# mainSchem.net
KiCad netlist of a schematic drawn in Altium Designer
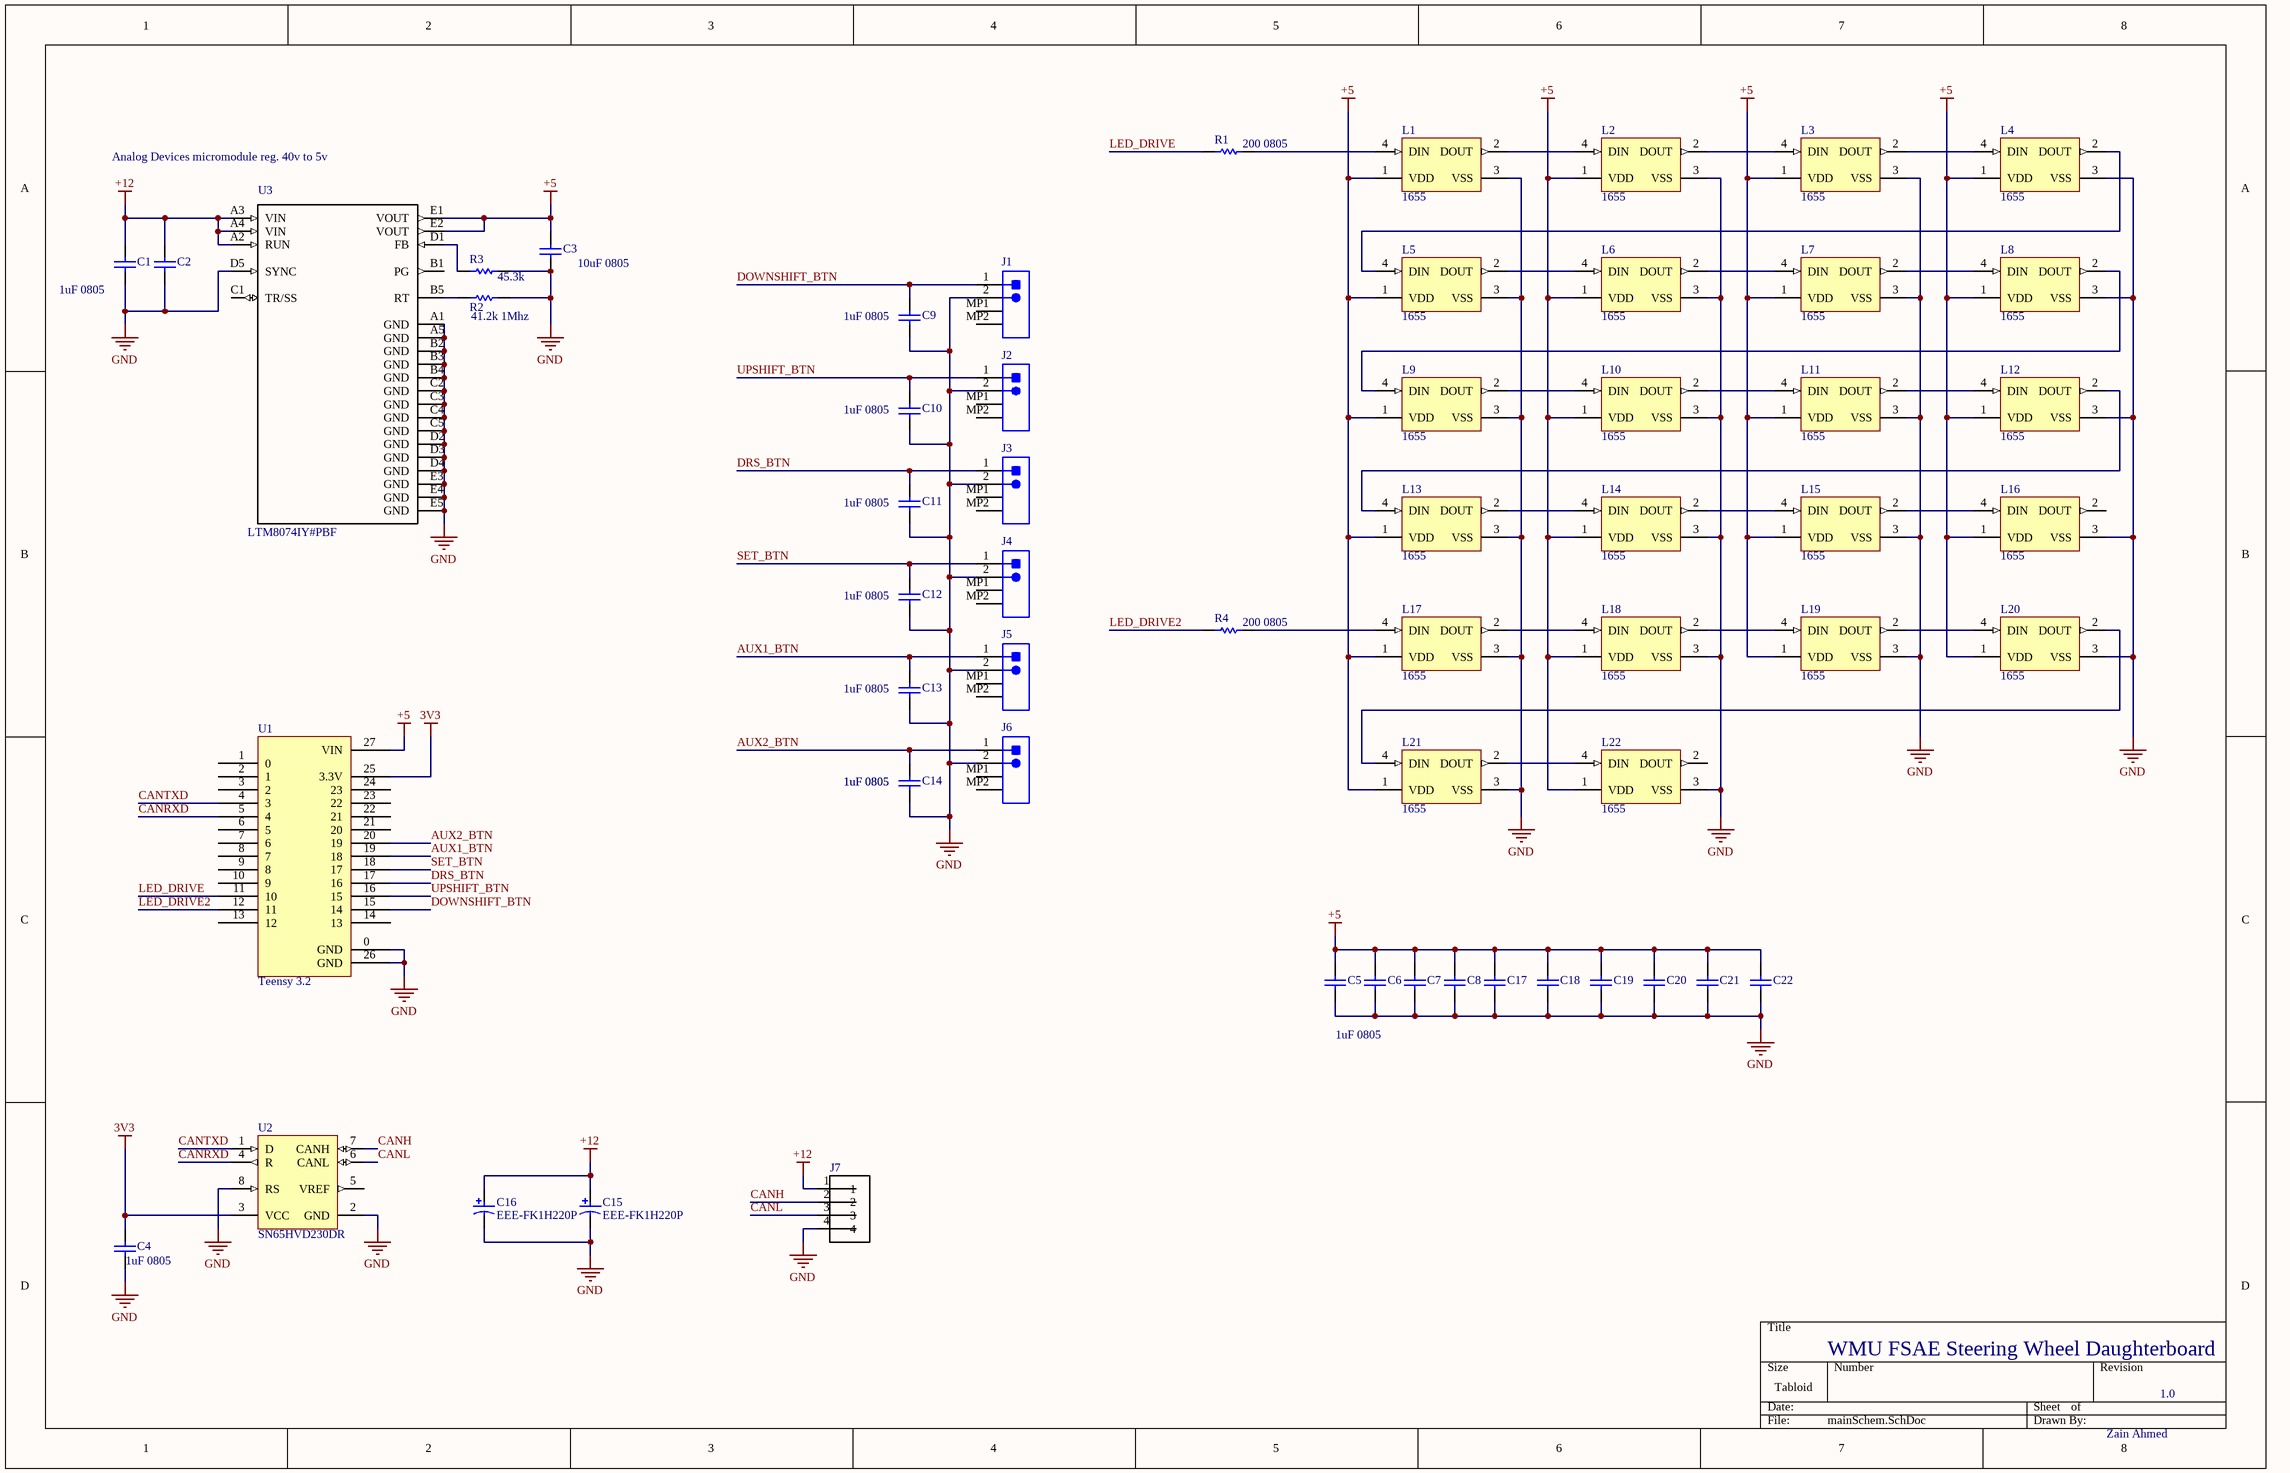
[diagram p0: mainSchem.SchDoc]

(export (version "E")
  (design (tool "Eeschema 10.0.6"))
  (components
    (comp (ref "C1")
      (value "GRM216R61E105KA12D")
      (footprint "CAPC2013X70X45NL10T25")
      (fields (field (name "MANUFACTURER") "Murata"))
      (libsource (lib "Altium Content Vault") (part "CAP"))
    )
    (comp (ref "C2")
      (value "GRM216R61E105KA12D")
      (footprint "CAPC2013X70X45NL10T25")
      (fields (field (name "MANUFACTURER") "Murata"))
      (libsource (lib "Altium Content Vault") (part "CAP"))
    )
    (comp (ref "C3")
      (value "GRM21BR61C106KE15L")
      (footprint "CAPC2013X135X50LL10T20")
      (fields (field (name "MANUFACTURER") "Murata"))
      (libsource (lib "Altium Content Vault") (part "CAP"))
    )
    (comp (ref "C4")
      (value "GRM216R61E105KA12D")
      (footprint "CAPC2013X70X45NL10T25")
      (fields (field (name "MANUFACTURER") "Murata"))
      (libsource (lib "Altium Content Vault") (part "CAP"))
    )
    (comp (ref "C5")
      (value "GRM216R61E105KA12D")
      (footprint "CAPC2013X70X45NL10T25")
      (fields (field (name "MANUFACTURER") "Murata"))
      (libsource (lib "Altium Content Vault") (part "CAP"))
    )
    (comp (ref "C6")
      (value "GRM216R61E105KA12D")
      (footprint "CAPC2013X70X45NL10T25")
      (fields (field (name "MANUFACTURER") "Murata"))
      (libsource (lib "Altium Content Vault") (part "CAP"))
    )
    (comp (ref "C7")
      (value "GRM216R61E105KA12D")
      (footprint "CAPC2013X70X45NL10T25")
      (fields (field (name "MANUFACTURER") "Murata"))
      (libsource (lib "Altium Content Vault") (part "CAP"))
    )
    (comp (ref "C8")
      (value "GRM216R61E105KA12D")
      (footprint "CAPC2013X70X45NL10T25")
      (fields (field (name "MANUFACTURER") "Murata"))
      (libsource (lib "Altium Content Vault") (part "CAP"))
    )
    (comp (ref "C9")
      (value "GRM216R61E105KA12D")
      (footprint "CAPC2013X70X45NL10T25")
      (fields (field (name "MANUFACTURER") "Murata"))
      (libsource (lib "Altium Content Vault") (part "CAP"))
    )
    (comp (ref "C10")
      (value "GRM216R61E105KA12D")
      (footprint "CAPC2013X70X45NL10T25")
      (fields (field (name "MANUFACTURER") "Murata"))
      (libsource (lib "Altium Content Vault") (part "CAP"))
    )
    (comp (ref "C11")
      (value "GRM216R61E105KA12D")
      (footprint "CAPC2013X70X45NL10T25")
      (fields (field (name "MANUFACTURER") "Murata"))
      (libsource (lib "Altium Content Vault") (part "CAP"))
    )
    (comp (ref "C12")
      (value "GRM216R61E105KA12D")
      (footprint "CAPC2013X70X45NL10T25")
      (fields (field (name "MANUFACTURER") "Murata"))
      (libsource (lib "Altium Content Vault") (part "CAP"))
    )
    (comp (ref "C13")
      (value "GRM216R61E105KA12D")
      (footprint "CAPC2013X70X45NL10T25")
      (fields (field (name "MANUFACTURER") "Murata"))
      (libsource (lib "Altium Content Vault") (part "CAP"))
    )
    (comp (ref "C14")
      (value "GRM216R61E105KA12D")
      (footprint "CAPC2013X70X45NL10T25")
      (fields (field (name "MANUFACTURER") "Murata"))
      (libsource (lib "Altium Content Vault") (part "CAP"))
    )
    (comp (ref "C15")
      (value "EEE-FK1H220P")
      (footprint "PNSC-EEE-FK1H220P_L")
      (description "Cap Aluminum Lytic, 22 uF, +/- 20%, 6.3 to 100 V, -55 to 105 degC, 2-Pin SMD, RoHS, Tape and Reel")
      (fields (field (name "MANUFACTURER") "Panasonic"))
      (libsource (lib "Altium Content Vault") (part "CAP-P-2"))
    )
    (comp (ref "C16")
      (value "EEE-FK1H220P")
      (footprint "PNSC-EEE-FK1H220P_L")
      (description "Cap Aluminum Lytic, 22 uF, +/- 20%, 6.3 to 100 V, -55 to 105 degC, 2-Pin SMD, RoHS, Tape and Reel")
      (fields (field (name "MANUFACTURER") "Panasonic"))
      (libsource (lib "Altium Content Vault") (part "CAP-P-2"))
    )
    (comp (ref "C17")
      (value "GRM216R61E105KA12D")
      (footprint "CAPC2013X70X45NL10T25")
      (fields (field (name "MANUFACTURER") "Murata"))
      (libsource (lib "Altium Content Vault") (part "CAP"))
    )
    (comp (ref "C18")
      (value "GRM216R61E105KA12D")
      (footprint "CAPC2013X70X45NL10T25")
      (fields (field (name "MANUFACTURER") "Murata"))
      (libsource (lib "Altium Content Vault") (part "CAP"))
    )
    (comp (ref "C19")
      (value "GRM216R61E105KA12D")
      (footprint "CAPC2013X70X45NL10T25")
      (fields (field (name "MANUFACTURER") "Murata"))
      (libsource (lib "Altium Content Vault") (part "CAP"))
    )
    (comp (ref "C20")
      (value "GRM216R61E105KA12D")
      (footprint "CAPC2013X70X45NL10T25")
      (fields (field (name "MANUFACTURER") "Murata"))
      (libsource (lib "Altium Content Vault") (part "CAP"))
    )
    (comp (ref "C21")
      (value "GRM216R61E105KA12D")
      (footprint "CAPC2013X70X45NL10T25")
      (fields (field (name "MANUFACTURER") "Murata"))
      (libsource (lib "Altium Content Vault") (part "CAP"))
    )
    (comp (ref "C22")
      (value "GRM216R61E105KA12D")
      (footprint "CAPC2013X70X45NL10T25")
      (fields (field (name "MANUFACTURER") "Murata"))
      (libsource (lib "Altium Content Vault") (part "CAP"))
    )
    (comp (ref "J1")
      (value "B2B-PH-SM4-TB(LF)(SN)")
      (footprint "JST-B2B-PH-SM4-TB-2_V")
      (description "Male Header, Pitch 2 mm, 1 x 2 Position, Height 6.6 mm, RoHS, Tape and Reel")
      (fields (field (name "MANUFACTURER") "JST"))
      (libsource (lib "Altium Content Vault") (part "CN-1P-2M-R2"))
    )
    (comp (ref "J2")
      (value "B2B-PH-SM4-TB(LF)(SN)")
      (footprint "JST-B2B-PH-SM4-TB-2_V")
      (description "Male Header, Pitch 2 mm, 1 x 2 Position, Height 6.6 mm, RoHS, Tape and Reel")
      (fields (field (name "MANUFACTURER") "JST"))
      (libsource (lib "Altium Content Vault") (part "CN-1P-2M-R2"))
    )
    (comp (ref "J3")
      (value "B2B-PH-SM4-TB(LF)(SN)")
      (footprint "JST-B2B-PH-SM4-TB-2_V")
      (description "Male Header, Pitch 2 mm, 1 x 2 Position, Height 6.6 mm, RoHS, Tape and Reel")
      (fields (field (name "MANUFACTURER") "JST"))
      (libsource (lib "Altium Content Vault") (part "CN-1P-2M-R2"))
    )
    (comp (ref "J4")
      (value "B2B-PH-SM4-TB(LF)(SN)")
      (footprint "JST-B2B-PH-SM4-TB-2_V")
      (description "Male Header, Pitch 2 mm, 1 x 2 Position, Height 6.6 mm, RoHS, Tape and Reel")
      (fields (field (name "MANUFACTURER") "JST"))
      (libsource (lib "Altium Content Vault") (part "CN-1P-2M-R2"))
    )
    (comp (ref "J5")
      (value "B2B-PH-SM4-TB(LF)(SN)")
      (footprint "JST-B2B-PH-SM4-TB-2_V")
      (description "Male Header, Pitch 2 mm, 1 x 2 Position, Height 6.6 mm, RoHS, Tape and Reel")
      (fields (field (name "MANUFACTURER") "JST"))
      (libsource (lib "Altium Content Vault") (part "CN-1P-2M-R2"))
    )
    (comp (ref "J6")
      (value "B2B-PH-SM4-TB(LF)(SN)")
      (footprint "JST-B2B-PH-SM4-TB-2_V")
      (description "Male Header, Pitch 2 mm, 1 x 2 Position, Height 6.6 mm, RoHS, Tape and Reel")
      (fields (field (name "MANUFACTURER") "JST"))
      (libsource (lib "Altium Content Vault") (part "CN-1P-2M-R2"))
    )
    (comp (ref "J7")
      (value "B4B-PH-SM4-TB")
      (footprint "*JST_B4B-PH-SM4-TB")
      (description "Connector Header Surface Mount 4 position 0.079 _2.00mm_")
      (fields (field (name "MF") "JST Sales"))
      (libsource (lib "B4B-PH-SM4-TB") (part "B4B-PH-SM4-TB"))
    )
    (comp (ref "L1")
      (value "1655")
      (footprint "ADA-RGB-1655_V")
      (fields (field (name "MANUFACTURER") "Adafruit-Industries-LLC"))
      (libsource (lib "Altium Content Vault") (part "ADA-RGB-1655-4"))
    )
    (comp (ref "L2")
      (value "1655")
      (footprint "ADA-RGB-1655_V")
      (fields (field (name "MANUFACTURER") "Adafruit-Industries-LLC"))
      (libsource (lib "Altium Content Vault") (part "ADA-RGB-1655-4"))
    )
    (comp (ref "L3")
      (value "1655")
      (footprint "ADA-RGB-1655_V")
      (fields (field (name "MANUFACTURER") "Adafruit-Industries-LLC"))
      (libsource (lib "Altium Content Vault") (part "ADA-RGB-1655-4"))
    )
    (comp (ref "L4")
      (value "1655")
      (footprint "ADA-RGB-1655_V")
      (fields (field (name "MANUFACTURER") "Adafruit-Industries-LLC"))
      (libsource (lib "Altium Content Vault") (part "ADA-RGB-1655-4"))
    )
    (comp (ref "L5")
      (value "1655")
      (footprint "ADA-RGB-1655_V")
      (fields (field (name "MANUFACTURER") "Adafruit-Industries-LLC"))
      (libsource (lib "Altium Content Vault") (part "ADA-RGB-1655-4"))
    )
    (comp (ref "L6")
      (value "1655")
      (footprint "ADA-RGB-1655_V")
      (fields (field (name "MANUFACTURER") "Adafruit-Industries-LLC"))
      (libsource (lib "Altium Content Vault") (part "ADA-RGB-1655-4"))
    )
    (comp (ref "L7")
      (value "1655")
      (footprint "ADA-RGB-1655_V")
      (fields (field (name "MANUFACTURER") "Adafruit-Industries-LLC"))
      (libsource (lib "Altium Content Vault") (part "ADA-RGB-1655-4"))
    )
    (comp (ref "L8")
      (value "1655")
      (footprint "ADA-RGB-1655_V")
      (fields (field (name "MANUFACTURER") "Adafruit-Industries-LLC"))
      (libsource (lib "Altium Content Vault") (part "ADA-RGB-1655-4"))
    )
    (comp (ref "L9")
      (value "1655")
      (footprint "ADA-RGB-1655_V")
      (fields (field (name "MANUFACTURER") "Adafruit-Industries-LLC"))
      (libsource (lib "Altium Content Vault") (part "ADA-RGB-1655-4"))
    )
    (comp (ref "L10")
      (value "1655")
      (footprint "ADA-RGB-1655_V")
      (fields (field (name "MANUFACTURER") "Adafruit-Industries-LLC"))
      (libsource (lib "Altium Content Vault") (part "ADA-RGB-1655-4"))
    )
    (comp (ref "L11")
      (value "1655")
      (footprint "ADA-RGB-1655_V")
      (fields (field (name "MANUFACTURER") "Adafruit-Industries-LLC"))
      (libsource (lib "Altium Content Vault") (part "ADA-RGB-1655-4"))
    )
    (comp (ref "L12")
      (value "1655")
      (footprint "ADA-RGB-1655_V")
      (fields (field (name "MANUFACTURER") "Adafruit-Industries-LLC"))
      (libsource (lib "Altium Content Vault") (part "ADA-RGB-1655-4"))
    )
    (comp (ref "L13")
      (value "1655")
      (footprint "ADA-RGB-1655_V")
      (fields (field (name "MANUFACTURER") "Adafruit-Industries-LLC"))
      (libsource (lib "Altium Content Vault") (part "ADA-RGB-1655-4"))
    )
    (comp (ref "L14")
      (value "1655")
      (footprint "ADA-RGB-1655_V")
      (fields (field (name "MANUFACTURER") "Adafruit-Industries-LLC"))
      (libsource (lib "Altium Content Vault") (part "ADA-RGB-1655-4"))
    )
    (comp (ref "L15")
      (value "1655")
      (footprint "ADA-RGB-1655_V")
      (fields (field (name "MANUFACTURER") "Adafruit-Industries-LLC"))
      (libsource (lib "Altium Content Vault") (part "ADA-RGB-1655-4"))
    )
    (comp (ref "L16")
      (value "1655")
      (footprint "ADA-RGB-1655_V")
      (fields (field (name "MANUFACTURER") "Adafruit-Industries-LLC"))
      (libsource (lib "Altium Content Vault") (part "ADA-RGB-1655-4"))
    )
    (comp (ref "L17")
      (value "1655")
      (footprint "ADA-RGB-1655_V")
      (fields (field (name "MANUFACTURER") "Adafruit-Industries-LLC"))
      (libsource (lib "Altium Content Vault") (part "ADA-RGB-1655-4"))
    )
    (comp (ref "L18")
      (value "1655")
      (footprint "ADA-RGB-1655_V")
      (fields (field (name "MANUFACTURER") "Adafruit-Industries-LLC"))
      (libsource (lib "Altium Content Vault") (part "ADA-RGB-1655-4"))
    )
    (comp (ref "L19")
      (value "1655")
      (footprint "ADA-RGB-1655_V")
      (fields (field (name "MANUFACTURER") "Adafruit-Industries-LLC"))
      (libsource (lib "Altium Content Vault") (part "ADA-RGB-1655-4"))
    )
    (comp (ref "L20")
      (value "1655")
      (footprint "ADA-RGB-1655_V")
      (fields (field (name "MANUFACTURER") "Adafruit-Industries-LLC"))
      (libsource (lib "Altium Content Vault") (part "ADA-RGB-1655-4"))
    )
    (comp (ref "L21")
      (value "1655")
      (footprint "ADA-RGB-1655_V")
      (fields (field (name "MANUFACTURER") "Adafruit-Industries-LLC"))
      (libsource (lib "Altium Content Vault") (part "ADA-RGB-1655-4"))
    )
    (comp (ref "L22")
      (value "1655")
      (footprint "ADA-RGB-1655_V")
      (fields (field (name "MANUFACTURER") "Adafruit-Industries-LLC"))
      (libsource (lib "Altium Content Vault") (part "ADA-RGB-1655-4"))
    )
    (comp (ref "R1")
      (value "ERA6AEB201V")
      (footprint "RESC2013X60X40NL20T25")
      (fields (field (name "MANUFACTURER") "Panasonic"))
      (libsource (lib "Altium Content Vault") (part "RES"))
    )
    (comp (ref "R2")
      (value "ERJ-6ENF4122V")
      (footprint "RESC2013X70X40LL20T20")
      (fields (field (name "MANUFACTURER") "Panasonic"))
      (libsource (lib "Altium Content Vault") (part "RES"))
    )
    (comp (ref "R3")
      (value "ERJ-6ENF4532V")
      (footprint "RESC2013X70X40ML20T20")
      (fields (field (name "MANUFACTURER") "Panasonic"))
      (libsource (lib "Altium Content Vault") (part "RES"))
    )
    (comp (ref "R4")
      (value "ERA6AEB201V")
      (footprint "RESC2013X60X40NL20T25")
      (fields (field (name "MANUFACTURER") "Panasonic"))
      (libsource (lib "Altium Content Vault") (part "RES"))
    )
    (comp (ref "U1")
      (value "Teensy 3.2")
      (footprint "Teensy3_2")
      (libsource (lib "Teensy3_2") (part "Teensy 3.2"))
    )
    (comp (ref "U2")
      (value "SN65HVD230DR")
      (footprint "D0008A_L")
      (fields (field (name "MANUFACTURER") "Texas Instruments"))
      (libsource (lib "Altium Content Vault") (part "TI-SN65HVD230-SOIC_D-8"))
    )
    (comp (ref "U3")
      (value "LTM8074IY#PBF")
      (footprint "*BGA25C65P5X5_400X400X198N_LTM8074IY#PBF(Primary)")
      (description "40Vin, 0.7A Step Dwn uModule Reg")
      (fields (field (name "MF") "Analog Devices"))
      (libsource (lib "LTM8074IY_PBF") (part "LTM8074IY#PBF"))
    )
  )
  (nets
    (net (code "1") (name "+5") (class "Default")
      (node (ref "C17") (pin "1") (pinfunction "1_1") (pintype "passive"))
      (node (ref "C18") (pin "1") (pinfunction "1_1") (pintype "passive"))
      (node (ref "C19") (pin "1") (pinfunction "1_1") (pintype "passive"))
      (node (ref "C20") (pin "1") (pinfunction "1_1") (pintype "passive"))
      (node (ref "C21") (pin "1") (pinfunction "1_1") (pintype "passive"))
      (node (ref "C22") (pin "1") (pinfunction "1_1") (pintype "passive"))
      (node (ref "C3") (pin "1") (pinfunction "1_1") (pintype "passive"))
      (node (ref "C5") (pin "1") (pinfunction "1_1") (pintype "passive"))
      (node (ref "C6") (pin "1") (pinfunction "1_1") (pintype "passive"))
      (node (ref "C7") (pin "1") (pinfunction "1_1") (pintype "passive"))
      (node (ref "C8") (pin "1") (pinfunction "1_1") (pintype "passive"))
      (node (ref "L1") (pin "1") (pinfunction "VDD_1") (pintype "power_in"))
      (node (ref "L10") (pin "1") (pinfunction "VDD_1") (pintype "power_in"))
      (node (ref "L11") (pin "1") (pinfunction "VDD_1") (pintype "power_in"))
      (node (ref "L12") (pin "1") (pinfunction "VDD_1") (pintype "power_in"))
      (node (ref "L13") (pin "1") (pinfunction "VDD_1") (pintype "power_in"))
      (node (ref "L14") (pin "1") (pinfunction "VDD_1") (pintype "power_in"))
      (node (ref "L15") (pin "1") (pinfunction "VDD_1") (pintype "power_in"))
      (node (ref "L16") (pin "1") (pinfunction "VDD_1") (pintype "power_in"))
      (node (ref "L17") (pin "1") (pinfunction "VDD_1") (pintype "power_in"))
      (node (ref "L18") (pin "1") (pinfunction "VDD_1") (pintype "power_in"))
      (node (ref "L19") (pin "1") (pinfunction "VDD_1") (pintype "power_in"))
      (node (ref "L2") (pin "1") (pinfunction "VDD_1") (pintype "power_in"))
      (node (ref "L20") (pin "1") (pinfunction "VDD_1") (pintype "power_in"))
      (node (ref "L21") (pin "1") (pinfunction "VDD_1") (pintype "power_in"))
      (node (ref "L22") (pin "1") (pinfunction "VDD_1") (pintype "power_in"))
      (node (ref "L3") (pin "1") (pinfunction "VDD_1") (pintype "power_in"))
      (node (ref "L4") (pin "1") (pinfunction "VDD_1") (pintype "power_in"))
      (node (ref "L5") (pin "1") (pinfunction "VDD_1") (pintype "power_in"))
      (node (ref "L6") (pin "1") (pinfunction "VDD_1") (pintype "power_in"))
      (node (ref "L7") (pin "1") (pinfunction "VDD_1") (pintype "power_in"))
      (node (ref "L8") (pin "1") (pinfunction "VDD_1") (pintype "power_in"))
      (node (ref "L9") (pin "1") (pinfunction "VDD_1") (pintype "power_in"))
      (node (ref "U1") (pin "27") (pinfunction "VIN_27") (pintype "passive"))
      (node (ref "U3") (pin "E1") (pinfunction "VOUT_E1") (pintype "output"))
      (node (ref "U3") (pin "E2") (pinfunction "VOUT_E2") (pintype "output"))
    )
    (net (code "2") (name "+12") (class "Default")
      (node (ref "C1") (pin "1") (pinfunction "1_1") (pintype "passive"))
      (node (ref "C15") (pin "1") (pinfunction "1_1") (pintype "passive"))
      (node (ref "C16") (pin "1") (pinfunction "1_1") (pintype "passive"))
      (node (ref "C2") (pin "1") (pinfunction "1_1") (pintype "passive"))
      (node (ref "J7") (pin "1") (pinfunction "1_1") (pintype "passive"))
      (node (ref "U3") (pin "A2") (pinfunction "RUN_A2") (pintype "input"))
      (node (ref "U3") (pin "A3") (pinfunction "VIN_A3") (pintype "input"))
      (node (ref "U3") (pin "A4") (pinfunction "VIN_A4") (pintype "input"))
    )
    (net (code "3") (name "/AUX1_BTN") (class "Default")
      (node (ref "C13") (pin "1") (pinfunction "1_1") (pintype "passive"))
      (node (ref "J5") (pin "1") (pinfunction "1_1") (pintype "passive"))
      (node (ref "U1") (pin "19") (pinfunction "18_19") (pintype "passive"))
    )
    (net (code "4") (name "/AUX2_BTN") (class "Default")
      (node (ref "C14") (pin "1") (pinfunction "1_1") (pintype "passive"))
      (node (ref "J6") (pin "1") (pinfunction "1_1") (pintype "passive"))
      (node (ref "U1") (pin "20") (pinfunction "19_20") (pintype "passive"))
    )
    (net (code "5") (name "/CANH") (class "Default")
      (node (ref "J7") (pin "2") (pinfunction "2_2") (pintype "passive"))
      (node (ref "U2") (pin "7") (pinfunction "CANH_7") (pintype "bidirectional"))
    )
    (net (code "6") (name "/CANL") (class "Default")
      (node (ref "J7") (pin "3") (pinfunction "3_3") (pintype "passive"))
      (node (ref "U2") (pin "6") (pinfunction "CANL_6") (pintype "bidirectional"))
    )
    (net (code "7") (name "/CANRXD") (class "Default")
      (node (ref "U1") (pin "5") (pinfunction "4_5") (pintype "passive"))
      (node (ref "U2") (pin "4") (pinfunction "R_4") (pintype "output"))
    )
    (net (code "8") (name "/CANTXD") (class "Default")
      (node (ref "U1") (pin "4") (pinfunction "3_4") (pintype "passive"))
      (node (ref "U2") (pin "1") (pinfunction "D_1") (pintype "input"))
    )
    (net (code "9") (name "/DOWNSHIFT_BTN") (class "Default")
      (node (ref "C9") (pin "1") (pinfunction "1_1") (pintype "passive"))
      (node (ref "J1") (pin "1") (pinfunction "1_1") (pintype "passive"))
      (node (ref "U1") (pin "15") (pinfunction "14_15") (pintype "passive"))
    )
    (net (code "10") (name "/DRS_BTN") (class "Default")
      (node (ref "C11") (pin "1") (pinfunction "1_1") (pintype "passive"))
      (node (ref "J3") (pin "1") (pinfunction "1_1") (pintype "passive"))
      (node (ref "U1") (pin "17") (pinfunction "16_17") (pintype "passive"))
    )
    (net (code "11") (name "/LED_DRIVE") (class "Default")
      (node (ref "R1") (pin "1") (pinfunction "1_1") (pintype "passive"))
      (node (ref "U1") (pin "11") (pinfunction "10_11") (pintype "passive"))
    )
    (net (code "12") (name "/LED_DRIVE2") (class "Default")
      (node (ref "R4") (pin "1") (pinfunction "1_1") (pintype "passive"))
      (node (ref "U1") (pin "12") (pinfunction "11_12") (pintype "passive"))
    )
    (net (code "13") (name "/SET_BTN") (class "Default")
      (node (ref "C12") (pin "1") (pinfunction "1_1") (pintype "passive"))
      (node (ref "J4") (pin "1") (pinfunction "1_1") (pintype "passive"))
      (node (ref "U1") (pin "18") (pinfunction "17_18") (pintype "passive"))
    )
    (net (code "14") (name "/UPSHIFT_BTN") (class "Default")
      (node (ref "C10") (pin "1") (pinfunction "1_1") (pintype "passive"))
      (node (ref "J2") (pin "1") (pinfunction "1_1") (pintype "passive"))
      (node (ref "U1") (pin "16") (pinfunction "15_16") (pintype "passive"))
    )
    (net (code "15") (name "3V3") (class "Default")
      (node (ref "C4") (pin "1") (pinfunction "1_1") (pintype "passive"))
      (node (ref "U1") (pin "25") (pinfunction "3.3V_25") (pintype "passive"))
      (node (ref "U2") (pin "3") (pinfunction "VCC_3") (pintype "power_in"))
    )
    (net (code "16") (name "GND") (class "Default")
      (node (ref "C1") (pin "2") (pinfunction "2_2") (pintype "passive"))
      (node (ref "C10") (pin "2") (pinfunction "2_2") (pintype "passive"))
      (node (ref "C11") (pin "2") (pinfunction "2_2") (pintype "passive"))
      (node (ref "C12") (pin "2") (pinfunction "2_2") (pintype "passive"))
      (node (ref "C13") (pin "2") (pinfunction "2_2") (pintype "passive"))
      (node (ref "C14") (pin "2") (pinfunction "2_2") (pintype "passive"))
      (node (ref "C15") (pin "2") (pinfunction "2_2") (pintype "passive"))
      (node (ref "C16") (pin "2") (pinfunction "2_2") (pintype "passive"))
      (node (ref "C17") (pin "2") (pinfunction "2_2") (pintype "passive"))
      (node (ref "C18") (pin "2") (pinfunction "2_2") (pintype "passive"))
      (node (ref "C19") (pin "2") (pinfunction "2_2") (pintype "passive"))
      (node (ref "C2") (pin "2") (pinfunction "2_2") (pintype "passive"))
      (node (ref "C20") (pin "2") (pinfunction "2_2") (pintype "passive"))
      (node (ref "C21") (pin "2") (pinfunction "2_2") (pintype "passive"))
      (node (ref "C22") (pin "2") (pinfunction "2_2") (pintype "passive"))
      (node (ref "C3") (pin "2") (pinfunction "2_2") (pintype "passive"))
      (node (ref "C4") (pin "2") (pinfunction "2_2") (pintype "passive"))
      (node (ref "C5") (pin "2") (pinfunction "2_2") (pintype "passive"))
      (node (ref "C6") (pin "2") (pinfunction "2_2") (pintype "passive"))
      (node (ref "C7") (pin "2") (pinfunction "2_2") (pintype "passive"))
      (node (ref "C8") (pin "2") (pinfunction "2_2") (pintype "passive"))
      (node (ref "C9") (pin "2") (pinfunction "2_2") (pintype "passive"))
      (node (ref "J1") (pin "2") (pinfunction "2_2") (pintype "passive"))
      (node (ref "J2") (pin "2") (pinfunction "2_2") (pintype "passive"))
      (node (ref "J3") (pin "2") (pinfunction "2_2") (pintype "passive"))
      (node (ref "J4") (pin "2") (pinfunction "2_2") (pintype "passive"))
      (node (ref "J5") (pin "2") (pinfunction "2_2") (pintype "passive"))
      (node (ref "J6") (pin "2") (pinfunction "2_2") (pintype "passive"))
      (node (ref "J7") (pin "4") (pinfunction "4_4") (pintype "passive"))
      (node (ref "L1") (pin "3") (pinfunction "VSS_3") (pintype "power_in"))
      (node (ref "L10") (pin "3") (pinfunction "VSS_3") (pintype "power_in"))
      (node (ref "L11") (pin "3") (pinfunction "VSS_3") (pintype "power_in"))
      (node (ref "L12") (pin "3") (pinfunction "VSS_3") (pintype "power_in"))
      (node (ref "L13") (pin "3") (pinfunction "VSS_3") (pintype "power_in"))
      (node (ref "L14") (pin "3") (pinfunction "VSS_3") (pintype "power_in"))
      (node (ref "L15") (pin "3") (pinfunction "VSS_3") (pintype "power_in"))
      (node (ref "L16") (pin "3") (pinfunction "VSS_3") (pintype "power_in"))
      (node (ref "L17") (pin "3") (pinfunction "VSS_3") (pintype "power_in"))
      (node (ref "L18") (pin "3") (pinfunction "VSS_3") (pintype "power_in"))
      (node (ref "L19") (pin "3") (pinfunction "VSS_3") (pintype "power_in"))
      (node (ref "L2") (pin "3") (pinfunction "VSS_3") (pintype "power_in"))
      (node (ref "L20") (pin "3") (pinfunction "VSS_3") (pintype "power_in"))
      (node (ref "L21") (pin "3") (pinfunction "VSS_3") (pintype "power_in"))
      (node (ref "L22") (pin "3") (pinfunction "VSS_3") (pintype "power_in"))
      (node (ref "L3") (pin "3") (pinfunction "VSS_3") (pintype "power_in"))
      (node (ref "L4") (pin "3") (pinfunction "VSS_3") (pintype "power_in"))
      (node (ref "L5") (pin "3") (pinfunction "VSS_3") (pintype "power_in"))
      (node (ref "L6") (pin "3") (pinfunction "VSS_3") (pintype "power_in"))
      (node (ref "L7") (pin "3") (pinfunction "VSS_3") (pintype "power_in"))
      (node (ref "L8") (pin "3") (pinfunction "VSS_3") (pintype "power_in"))
      (node (ref "L9") (pin "3") (pinfunction "VSS_3") (pintype "power_in"))
      (node (ref "R2") (pin "2") (pinfunction "2_2") (pintype "passive"))
      (node (ref "R3") (pin "2") (pinfunction "2_2") (pintype "passive"))
      (node (ref "U1") (pin "0") (pinfunction "GND_0") (pintype "passive"))
      (node (ref "U1") (pin "26") (pinfunction "GND_26") (pintype "passive"))
      (node (ref "U2") (pin "2") (pinfunction "GND_2") (pintype "power_in"))
      (node (ref "U2") (pin "8") (pinfunction "RS_8") (pintype "input"))
      (node (ref "U3") (pin "A1") (pinfunction "GND_A1") (pintype "power_in"))
      (node (ref "U3") (pin "A5") (pinfunction "GND_A5") (pintype "power_in"))
      (node (ref "U3") (pin "B2") (pinfunction "GND_B2") (pintype "power_in"))
      (node (ref "U3") (pin "B3") (pinfunction "GND_B3") (pintype "power_in"))
      (node (ref "U3") (pin "B4") (pinfunction "GND_B4") (pintype "power_in"))
      (node (ref "U3") (pin "C2") (pinfunction "GND_C2") (pintype "power_in"))
      (node (ref "U3") (pin "C3") (pinfunction "GND_C3") (pintype "power_in"))
      (node (ref "U3") (pin "C4") (pinfunction "GND_C4") (pintype "power_in"))
      (node (ref "U3") (pin "C5") (pinfunction "GND_C5") (pintype "power_in"))
      (node (ref "U3") (pin "D2") (pinfunction "GND_D2") (pintype "power_in"))
      (node (ref "U3") (pin "D3") (pinfunction "GND_D3") (pintype "power_in"))
      (node (ref "U3") (pin "D4") (pinfunction "GND_D4") (pintype "power_in"))
      (node (ref "U3") (pin "D5") (pinfunction "SYNC_D5") (pintype "input"))
      (node (ref "U3") (pin "E3") (pinfunction "GND_E3") (pintype "power_in"))
      (node (ref "U3") (pin "E4") (pinfunction "GND_E4") (pintype "power_in"))
      (node (ref "U3") (pin "E5") (pinfunction "GND_E5") (pintype "power_in"))
    )
    (net (code "17") (name "Net-(L1-DIN)") (class "Default")
      (node (ref "L1") (pin "4") (pinfunction "DIN_4") (pintype "input"))
      (node (ref "R1") (pin "2") (pinfunction "2_2") (pintype "passive"))
    )
    (net (code "18") (name "Net-(L1-DOUT)") (class "Default")
      (node (ref "L1") (pin "2") (pinfunction "DOUT_2") (pintype "output"))
      (node (ref "L2") (pin "4") (pinfunction "DIN_4") (pintype "input"))
    )
    (net (code "19") (name "Net-(L2-DOUT)") (class "Default")
      (node (ref "L2") (pin "2") (pinfunction "DOUT_2") (pintype "output"))
      (node (ref "L3") (pin "4") (pinfunction "DIN_4") (pintype "input"))
    )
    (net (code "20") (name "Net-(L3-DOUT)") (class "Default")
      (node (ref "L3") (pin "2") (pinfunction "DOUT_2") (pintype "output"))
      (node (ref "L4") (pin "4") (pinfunction "DIN_4") (pintype "input"))
    )
    (net (code "21") (name "Net-(L4-DOUT)") (class "Default")
      (node (ref "L4") (pin "2") (pinfunction "DOUT_2") (pintype "output"))
      (node (ref "L5") (pin "4") (pinfunction "DIN_4") (pintype "input"))
    )
    (net (code "22") (name "Net-(L5-DOUT)") (class "Default")
      (node (ref "L5") (pin "2") (pinfunction "DOUT_2") (pintype "output"))
      (node (ref "L6") (pin "4") (pinfunction "DIN_4") (pintype "input"))
    )
    (net (code "23") (name "Net-(L6-DOUT)") (class "Default")
      (node (ref "L6") (pin "2") (pinfunction "DOUT_2") (pintype "output"))
      (node (ref "L7") (pin "4") (pinfunction "DIN_4") (pintype "input"))
    )
    (net (code "24") (name "Net-(L7-DOUT)") (class "Default")
      (node (ref "L7") (pin "2") (pinfunction "DOUT_2") (pintype "output"))
      (node (ref "L8") (pin "4") (pinfunction "DIN_4") (pintype "input"))
    )
    (net (code "25") (name "Net-(L8-DOUT)") (class "Default")
      (node (ref "L8") (pin "2") (pinfunction "DOUT_2") (pintype "output"))
      (node (ref "L9") (pin "4") (pinfunction "DIN_4") (pintype "input"))
    )
    (net (code "26") (name "Net-(L10-DIN)") (class "Default")
      (node (ref "L10") (pin "4") (pinfunction "DIN_4") (pintype "input"))
      (node (ref "L9") (pin "2") (pinfunction "DOUT_2") (pintype "output"))
    )
    (net (code "27") (name "Net-(L10-DOUT)") (class "Default")
      (node (ref "L10") (pin "2") (pinfunction "DOUT_2") (pintype "output"))
      (node (ref "L11") (pin "4") (pinfunction "DIN_4") (pintype "input"))
    )
    (net (code "28") (name "Net-(L11-DOUT)") (class "Default")
      (node (ref "L11") (pin "2") (pinfunction "DOUT_2") (pintype "output"))
      (node (ref "L12") (pin "4") (pinfunction "DIN_4") (pintype "input"))
    )
    (net (code "29") (name "Net-(L12-DOUT)") (class "Default")
      (node (ref "L12") (pin "2") (pinfunction "DOUT_2") (pintype "output"))
      (node (ref "L13") (pin "4") (pinfunction "DIN_4") (pintype "input"))
    )
    (net (code "30") (name "Net-(L13-DOUT)") (class "Default")
      (node (ref "L13") (pin "2") (pinfunction "DOUT_2") (pintype "output"))
      (node (ref "L14") (pin "4") (pinfunction "DIN_4") (pintype "input"))
    )
    (net (code "31") (name "Net-(L14-DOUT)") (class "Default")
      (node (ref "L14") (pin "2") (pinfunction "DOUT_2") (pintype "output"))
      (node (ref "L15") (pin "4") (pinfunction "DIN_4") (pintype "input"))
    )
    (net (code "32") (name "Net-(L15-DOUT)") (class "Default")
      (node (ref "L15") (pin "2") (pinfunction "DOUT_2") (pintype "output"))
      (node (ref "L16") (pin "4") (pinfunction "DIN_4") (pintype "input"))
    )
    (net (code "33") (name "Net-(L17-DIN)") (class "Default")
      (node (ref "L17") (pin "4") (pinfunction "DIN_4") (pintype "input"))
      (node (ref "R4") (pin "2") (pinfunction "2_2") (pintype "passive"))
    )
    (net (code "34") (name "Net-(L17-DOUT)") (class "Default")
      (node (ref "L17") (pin "2") (pinfunction "DOUT_2") (pintype "output"))
      (node (ref "L18") (pin "4") (pinfunction "DIN_4") (pintype "input"))
    )
    (net (code "35") (name "Net-(L18-DOUT)") (class "Default")
      (node (ref "L18") (pin "2") (pinfunction "DOUT_2") (pintype "output"))
      (node (ref "L19") (pin "4") (pinfunction "DIN_4") (pintype "input"))
    )
    (net (code "36") (name "Net-(L19-DOUT)") (class "Default")
      (node (ref "L19") (pin "2") (pinfunction "DOUT_2") (pintype "output"))
      (node (ref "L20") (pin "4") (pinfunction "DIN_4") (pintype "input"))
    )
    (net (code "37") (name "Net-(L20-DOUT)") (class "Default")
      (node (ref "L20") (pin "2") (pinfunction "DOUT_2") (pintype "output"))
      (node (ref "L21") (pin "4") (pinfunction "DIN_4") (pintype "input"))
    )
    (net (code "38") (name "Net-(L21-DOUT)") (class "Default")
      (node (ref "L21") (pin "2") (pinfunction "DOUT_2") (pintype "output"))
      (node (ref "L22") (pin "4") (pinfunction "DIN_4") (pintype "input"))
    )
    (net (code "39") (name "Net-(U3-FB)") (class "Default")
      (node (ref "R3") (pin "1") (pinfunction "1_1") (pintype "passive"))
      (node (ref "U3") (pin "D1") (pinfunction "FB_D1") (pintype "input"))
    )
    (net (code "40") (name "Net-(U3-RT)") (class "Default")
      (node (ref "R2") (pin "1") (pinfunction "1_1") (pintype "passive"))
      (node (ref "U3") (pin "B5") (pinfunction "RT_B5") (pintype "passive"))
    )
    (net (code "41") (name "unconnected-(J1-PadMP1)") (class "Default")
      (node (ref "J1") (pin "MP1") (pinfunction "MP1_MP1") (pintype "passive"))
    )
    (net (code "42") (name "unconnected-(J1-PadMP2)") (class "Default")
      (node (ref "J1") (pin "MP2") (pinfunction "MP2_MP2") (pintype "passive"))
    )
    (net (code "43") (name "unconnected-(J2-PadMP1)") (class "Default")
      (node (ref "J2") (pin "MP1") (pinfunction "MP1_MP1") (pintype "passive"))
    )
    (net (code "44") (name "unconnected-(J2-PadMP2)") (class "Default")
      (node (ref "J2") (pin "MP2") (pinfunction "MP2_MP2") (pintype "passive"))
    )
    (net (code "45") (name "unconnected-(J3-PadMP1)") (class "Default")
      (node (ref "J3") (pin "MP1") (pinfunction "MP1_MP1") (pintype "passive"))
    )
    (net (code "46") (name "unconnected-(J3-PadMP2)") (class "Default")
      (node (ref "J3") (pin "MP2") (pinfunction "MP2_MP2") (pintype "passive"))
    )
    (net (code "47") (name "unconnected-(J4-PadMP1)") (class "Default")
      (node (ref "J4") (pin "MP1") (pinfunction "MP1_MP1") (pintype "passive"))
    )
    (net (code "48") (name "unconnected-(J4-PadMP2)") (class "Default")
      (node (ref "J4") (pin "MP2") (pinfunction "MP2_MP2") (pintype "passive"))
    )
    (net (code "49") (name "unconnected-(J5-PadMP1)") (class "Default")
      (node (ref "J5") (pin "MP1") (pinfunction "MP1_MP1") (pintype "passive"))
    )
    (net (code "50") (name "unconnected-(J5-PadMP2)") (class "Default")
      (node (ref "J5") (pin "MP2") (pinfunction "MP2_MP2") (pintype "passive"))
    )
    (net (code "51") (name "unconnected-(J6-PadMP1)") (class "Default")
      (node (ref "J6") (pin "MP1") (pinfunction "MP1_MP1") (pintype "passive"))
    )
    (net (code "52") (name "unconnected-(J6-PadMP2)") (class "Default")
      (node (ref "J6") (pin "MP2") (pinfunction "MP2_MP2") (pintype "passive"))
    )
    (net (code "53") (name "unconnected-(L16-DOUT-Pad2)") (class "Default")
      (node (ref "L16") (pin "2") (pinfunction "DOUT_2") (pintype "output"))
    )
    (net (code "54") (name "unconnected-(L22-DOUT-Pad2)") (class "Default")
      (node (ref "L22") (pin "2") (pinfunction "DOUT_2") (pintype "output"))
    )
    (net (code "55") (name "unconnected-(U1-0-Pad1)") (class "Default")
      (node (ref "U1") (pin "1") (pinfunction "0_1") (pintype "passive"))
    )
    (net (code "56") (name "unconnected-(U1-1-Pad2)") (class "Default")
      (node (ref "U1") (pin "2") (pinfunction "1_2") (pintype "passive"))
    )
    (net (code "57") (name "unconnected-(U1-2-Pad3)") (class "Default")
      (node (ref "U1") (pin "3") (pinfunction "2_3") (pintype "passive"))
    )
    (net (code "58") (name "unconnected-(U1-5-Pad6)") (class "Default")
      (node (ref "U1") (pin "6") (pinfunction "5_6") (pintype "passive"))
    )
    (net (code "59") (name "unconnected-(U1-6-Pad7)") (class "Default")
      (node (ref "U1") (pin "7") (pinfunction "6_7") (pintype "passive"))
    )
    (net (code "60") (name "unconnected-(U1-7-Pad8)") (class "Default")
      (node (ref "U1") (pin "8") (pinfunction "7_8") (pintype "passive"))
    )
    (net (code "61") (name "unconnected-(U1-8-Pad9)") (class "Default")
      (node (ref "U1") (pin "9") (pinfunction "8_9") (pintype "passive"))
    )
    (net (code "62") (name "unconnected-(U1-9-Pad10)") (class "Default")
      (node (ref "U1") (pin "10") (pinfunction "9_10") (pintype "passive"))
    )
    (net (code "63") (name "unconnected-(U1-12-Pad13)") (class "Default")
      (node (ref "U1") (pin "13") (pinfunction "12_13") (pintype "passive"))
    )
    (net (code "64") (name "unconnected-(U1-13-Pad14)") (class "Default")
      (node (ref "U1") (pin "14") (pinfunction "13_14") (pintype "passive"))
    )
    (net (code "65") (name "unconnected-(U1-20-Pad21)") (class "Default")
      (node (ref "U1") (pin "21") (pinfunction "20_21") (pintype "passive"))
    )
    (net (code "66") (name "unconnected-(U1-21-Pad22)") (class "Default")
      (node (ref "U1") (pin "22") (pinfunction "21_22") (pintype "passive"))
    )
    (net (code "67") (name "unconnected-(U1-22-Pad23)") (class "Default")
      (node (ref "U1") (pin "23") (pinfunction "22_23") (pintype "passive"))
    )
    (net (code "68") (name "unconnected-(U1-23-Pad24)") (class "Default")
      (node (ref "U1") (pin "24") (pinfunction "23_24") (pintype "passive"))
    )
    (net (code "69") (name "unconnected-(U2-VREF-Pad5)") (class "Default")
      (node (ref "U2") (pin "5") (pinfunction "VREF_5") (pintype "output"))
    )
    (net (code "70") (name "unconnected-(U3-PG-PadB1)") (class "Default")
      (node (ref "U3") (pin "B1") (pinfunction "PG_B1") (pintype "output"))
    )
    (net (code "71") (name "unconnected-(U3-TR{slash}SS-PadC1)") (class "Default")
      (node (ref "U3") (pin "C1") (pinfunction "TR/SS_C1") (pintype "bidirectional"))
    )
  )
)
